# 2SiPM_4.net
KiCad netlist of a schematic drawn in Altium Designer
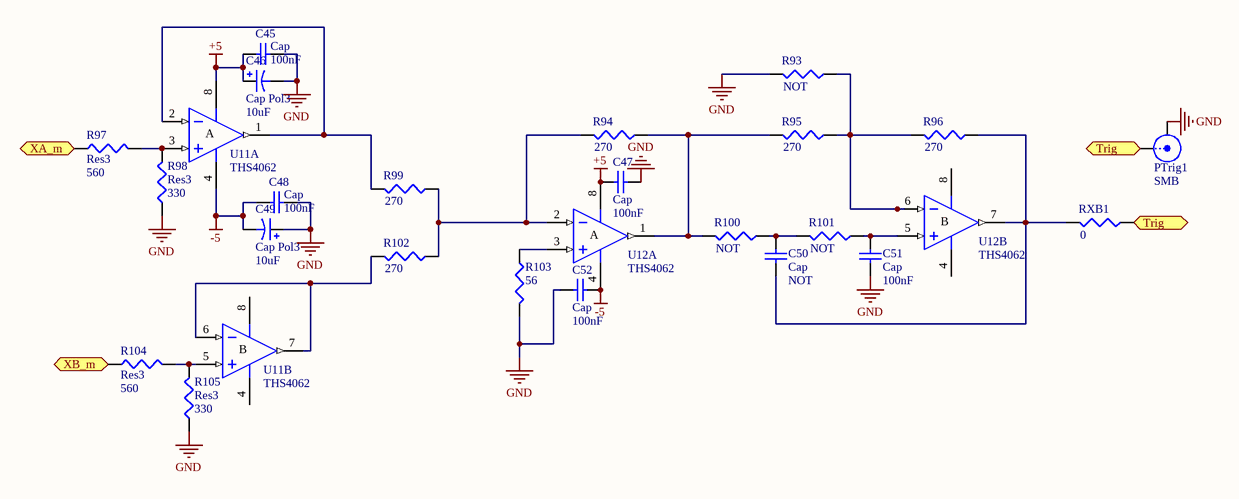
[diagram p0: 2SiPM_4.SchDoc]

(export (version "E")
  (design (tool "Eeschema 10.0.6"))
  (components
    (comp (ref "C45")
      (value "Cap")
      (footprint "6-0805_N")
      (description "Capacitor")
      (fields (field (name "ALTIUM_VALUE") "100nF") (field (name "PUBLISHER") "Altium Limited"))
      (libsource (lib "Miscellaneous Devices") (part "Cap"))
    )
    (comp (ref "C46")
      (value "Cap Pol3")
      (footprint "6-0805_N")
      (description "Polarized Capacitor (Surface Mount)")
      (fields (field (name "ALTIUM_VALUE") "10uF") (field (name "PUBLISHER") "Altium Limited"))
      (libsource (lib "Miscellaneous Devices") (part "Cap Pol3"))
    )
    (comp (ref "C47")
      (value "Cap")
      (footprint "1608[0603]")
      (description "Capacitor")
      (fields (field (name "ALTIUM_VALUE") "100nF") (field (name "PUBLISHER") "Altium Limited"))
      (libsource (lib "Miscellaneous Devices") (part "Cap"))
    )
    (comp (ref "C48")
      (value "Cap")
      (footprint "6-0805_N")
      (description "Capacitor")
      (fields (field (name "ALTIUM_VALUE") "100nF") (field (name "PUBLISHER") "Altium Limited"))
      (libsource (lib "Miscellaneous Devices") (part "Cap"))
    )
    (comp (ref "C49")
      (value "Cap Pol3")
      (footprint "6-0805_N")
      (description "Polarized Capacitor (Surface Mount)")
      (fields (field (name "ALTIUM_VALUE") "10uF") (field (name "PUBLISHER") "Altium Limited"))
      (libsource (lib "Miscellaneous Devices") (part "Cap Pol3"))
    )
    (comp (ref "C50")
      (value "Cap")
      (footprint "1608[0603]")
      (description "Capacitor")
      (fields (field (name "ALTIUM_VALUE") "NOT") (field (name "PUBLISHER") "Altium Limited"))
      (libsource (lib "Miscellaneous Devices") (part "Cap"))
    )
    (comp (ref "C51")
      (value "Cap")
      (footprint "1608[0603]")
      (description "Capacitor")
      (fields (field (name "ALTIUM_VALUE") "100nF") (field (name "PUBLISHER") "Altium Limited"))
      (libsource (lib "Miscellaneous Devices") (part "Cap"))
    )
    (comp (ref "C52")
      (value "Cap")
      (footprint "1608[0603]")
      (description "Capacitor")
      (fields (field (name "ALTIUM_VALUE") "100nF") (field (name "PUBLISHER") "Altium Limited"))
      (libsource (lib "Miscellaneous Devices") (part "Cap"))
    )
    (comp (ref "PTrig1")
      (value "SMB")
      (footprint "SMB_V-RJ45")
      (description "SMB Straight Connector")
      (fields (field (name "PUBLISHER") "Altium Limited"))
      (libsource (lib "Miscellaneous Connectors") (part "SMB"))
    )
    (comp (ref "R93")
      (value "NOT")
      (footprint "J1-0603")
      (description "Resistor")
      (fields (field (name "Comment") "Res3") (field (name "PUBLISHER") "Altium Limited"))
      (libsource (lib "Miscellaneous Devices") (part "Res3"))
    )
    (comp (ref "R94")
      (value "270")
      (footprint "J1-0603")
      (description "Resistor")
      (fields (field (name "Comment") "Res3") (field (name "PUBLISHER") "Altium Limited"))
      (libsource (lib "Miscellaneous Devices") (part "Res3"))
    )
    (comp (ref "R95")
      (value "270")
      (footprint "J1-0603")
      (description "Resistor")
      (fields (field (name "Comment") "Res3") (field (name "PUBLISHER") "Altium Limited"))
      (libsource (lib "Miscellaneous Devices") (part "Res3"))
    )
    (comp (ref "R96")
      (value "270")
      (footprint "J1-0603")
      (description "Resistor")
      (fields (field (name "Comment") "Res3") (field (name "PUBLISHER") "Altium Limited"))
      (libsource (lib "Miscellaneous Devices") (part "Res3"))
    )
    (comp (ref "R97")
      (value "Res3")
      (footprint "J1-0603")
      (description "Resistor")
      (fields (field (name "ALTIUM_VALUE") "560") (field (name "PUBLISHER") "Altium Limited"))
      (libsource (lib "Miscellaneous Devices") (part "Res3"))
    )
    (comp (ref "R98")
      (value "Res3")
      (footprint "J1-0603")
      (description "Resistor")
      (fields (field (name "ALTIUM_VALUE") "330") (field (name "PUBLISHER") "Altium Limited"))
      (libsource (lib "Miscellaneous Devices") (part "Res3"))
    )
    (comp (ref "R99")
      (value "270")
      (footprint "J1-0603")
      (description "Resistor")
      (fields (field (name "Comment") "Res3") (field (name "PUBLISHER") "Altium Limited"))
      (libsource (lib "Miscellaneous Devices") (part "Res3"))
    )
    (comp (ref "R100")
      (value "NOT")
      (footprint "J1-0603")
      (description "Resistor")
      (fields (field (name "Comment") "Res3") (field (name "PUBLISHER") "Altium Limited"))
      (libsource (lib "Miscellaneous Devices") (part "Res3"))
    )
    (comp (ref "R101")
      (value "NOT")
      (footprint "J1-0603")
      (description "Resistor")
      (fields (field (name "Comment") "Res3") (field (name "PUBLISHER") "Altium Limited"))
      (libsource (lib "Miscellaneous Devices") (part "Res3"))
    )
    (comp (ref "R102")
      (value "270")
      (footprint "J1-0603")
      (description "Resistor")
      (fields (field (name "Comment") "Res3") (field (name "PUBLISHER") "Altium Limited"))
      (libsource (lib "Miscellaneous Devices") (part "Res3"))
    )
    (comp (ref "R103")
      (value "56")
      (footprint "J1-0603")
      (description "Resistor")
      (fields (field (name "Comment") "Res3") (field (name "PUBLISHER") "Altium Limited"))
      (libsource (lib "Miscellaneous Devices") (part "Res3"))
    )
    (comp (ref "R104")
      (value "Res3")
      (footprint "J1-0603")
      (description "Resistor")
      (fields (field (name "ALTIUM_VALUE") "560") (field (name "PUBLISHER") "Altium Limited"))
      (libsource (lib "Miscellaneous Devices") (part "Res3"))
    )
    (comp (ref "R105")
      (value "Res3")
      (footprint "J1-0603")
      (description "Resistor")
      (fields (field (name "ALTIUM_VALUE") "330") (field (name "PUBLISHER") "Altium Limited"))
      (libsource (lib "Miscellaneous Devices") (part "Res3"))
    )
    (comp (ref "RXB1")
      (value "0")
      (footprint "J1-0603")
      (description "Resistor")
      (fields (field (name "Comment") "Res3") (field (name "PUBLISHER") "Altium Limited"))
      (libsource (lib "Miscellaneous Devices") (part "Res3"))
    )
    (comp (ref "U11")
      (value "THS4062")
      (footprint "SO-8_M")
      (description "Dual 600MHz, 50mW Current Feedback Amplifier")
      (fields (field (name "PUBLISHER") "Altium Limited"))
      (libsource (lib "AD Operational Amplifier") (part "AD8002AR"))
    )
    (comp (ref "U12")
      (value "THS4062")
      (footprint "SO8_M")
      (description "Low Cost, 300MHz Voltage Feedback Amplifier")
      (fields (field (name "PUBLISHER") "Altium Limited"))
      (libsource (lib "AD Operational Amplifier") (part "AD8056ARM"))
    )
  )
  (nets
    (net (code "1") (name "+5") (class "Default")
      (node (ref "C45") (pin "2") (pinfunction "2_2") (pintype "passive"))
      (node (ref "C46") (pin "1") (pinfunction "1_1") (pintype "passive"))
      (node (ref "C47") (pin "1") (pinfunction "1_1") (pintype "passive"))
      (node (ref "U11") (pin "8") (pinfunction "V+_8") (pintype "power_in"))
      (node (ref "U12") (pin "8") (pinfunction "V+_8") (pintype "power_in"))
    )
    (net (code "2") (name "-5") (class "Default")
      (node (ref "C48") (pin "2") (pinfunction "2_2") (pintype "passive"))
      (node (ref "C49") (pin "2") (pinfunction "2_2") (pintype "passive"))
      (node (ref "C52") (pin "2") (pinfunction "2_2") (pintype "passive"))
      (node (ref "U11") (pin "4") (pinfunction "V-_4") (pintype "power_in"))
      (node (ref "U12") (pin "4") (pinfunction "V-_4") (pintype "power_in"))
    )
    (net (code "3") (name "/Trig") (class "Default")
      (node (ref "PTrig1") (pin "1") (pinfunction "X_1") (pintype "passive"))
      (node (ref "RXB1") (pin "1") (pinfunction "1_1") (pintype "passive"))
    )
    (net (code "4") (name "/XA_m") (class "Default")
      (node (ref "R97") (pin "1") (pinfunction "1_1") (pintype "passive"))
    )
    (net (code "5") (name "/XB_m") (class "Default")
      (node (ref "R104") (pin "1") (pinfunction "1_1") (pintype "passive"))
    )
    (net (code "6") (name "GND") (class "Default")
      (node (ref "C45") (pin "1") (pinfunction "1_1") (pintype "passive"))
      (node (ref "C46") (pin "2") (pinfunction "2_2") (pintype "passive"))
      (node (ref "C47") (pin "2") (pinfunction "2_2") (pintype "passive"))
      (node (ref "C48") (pin "1") (pinfunction "1_1") (pintype "passive"))
      (node (ref "C49") (pin "1") (pinfunction "1_1") (pintype "passive"))
      (node (ref "C51") (pin "2") (pinfunction "2_2") (pintype "passive"))
      (node (ref "C52") (pin "1") (pinfunction "1_1") (pintype "passive"))
      (node (ref "PTrig1") (pin "2") (pinfunction "Y_2") (pintype "passive"))
      (node (ref "R103") (pin "2") (pinfunction "2_2") (pintype "passive"))
      (node (ref "R105") (pin "1") (pinfunction "1_1") (pintype "passive"))
      (node (ref "R93") (pin "2") (pinfunction "2_2") (pintype "passive"))
      (node (ref "R98") (pin "1") (pinfunction "1_1") (pintype "passive"))
    )
    (net (code "7") (name "Net-(C50-Pad1)") (class "Default")
      (node (ref "C50") (pin "1") (pinfunction "1_1") (pintype "passive"))
      (node (ref "R100") (pin "1") (pinfunction "1_1") (pintype "passive"))
      (node (ref "R101") (pin "2") (pinfunction "2_2") (pintype "passive"))
    )
    (net (code "8") (name "Net-(U11A-IN+)") (class "Default")
      (node (ref "R97") (pin "2") (pinfunction "2_2") (pintype "passive"))
      (node (ref "R98") (pin "2") (pinfunction "2_2") (pintype "passive"))
      (node (ref "U11") (pin "3") (pinfunction "IN+_3") (pintype "input"))
    )
    (net (code "9") (name "Net-(U11A-IN-)") (class "Default")
      (node (ref "R99") (pin "2") (pinfunction "2_2") (pintype "passive"))
      (node (ref "U11") (pin "1") (pinfunction "OUT_1") (pintype "output"))
      (node (ref "U11") (pin "2") (pinfunction "IN-_2") (pintype "input"))
    )
    (net (code "10") (name "Net-(U11B-IN+)") (class "Default")
      (node (ref "R104") (pin "2") (pinfunction "2_2") (pintype "passive"))
      (node (ref "R105") (pin "2") (pinfunction "2_2") (pintype "passive"))
      (node (ref "U11") (pin "5") (pinfunction "IN+_5") (pintype "input"))
    )
    (net (code "11") (name "Net-(U11B-IN-)") (class "Default")
      (node (ref "R102") (pin "2") (pinfunction "2_2") (pintype "passive"))
      (node (ref "U11") (pin "6") (pinfunction "IN-_6") (pintype "input"))
      (node (ref "U11") (pin "7") (pinfunction "OUT_7") (pintype "output"))
    )
    (net (code "12") (name "Net-(U12A-IN+)") (class "Default")
      (node (ref "R103") (pin "1") (pinfunction "1_1") (pintype "passive"))
      (node (ref "U12") (pin "3") (pinfunction "IN+_3") (pintype "input"))
    )
    (net (code "13") (name "Net-(U12A-IN-)") (class "Default")
      (node (ref "R102") (pin "1") (pinfunction "1_1") (pintype "passive"))
      (node (ref "R94") (pin "2") (pinfunction "2_2") (pintype "passive"))
      (node (ref "R99") (pin "1") (pinfunction "1_1") (pintype "passive"))
      (node (ref "U12") (pin "2") (pinfunction "IN-_2") (pintype "input"))
    )
    (net (code "14") (name "Net-(U12A-OUT)") (class "Default")
      (node (ref "R100") (pin "2") (pinfunction "2_2") (pintype "passive"))
      (node (ref "R94") (pin "1") (pinfunction "1_1") (pintype "passive"))
      (node (ref "R95") (pin "2") (pinfunction "2_2") (pintype "passive"))
      (node (ref "U12") (pin "1") (pinfunction "OUT_1") (pintype "output"))
    )
    (net (code "15") (name "Net-(U12B-IN+)") (class "Default")
      (node (ref "C51") (pin "1") (pinfunction "1_1") (pintype "passive"))
      (node (ref "R101") (pin "1") (pinfunction "1_1") (pintype "passive"))
      (node (ref "U12") (pin "5") (pinfunction "IN+_5") (pintype "input"))
    )
    (net (code "16") (name "Net-(U12B-IN-)") (class "Default")
      (node (ref "R93") (pin "1") (pinfunction "1_1") (pintype "passive"))
      (node (ref "R95") (pin "1") (pinfunction "1_1") (pintype "passive"))
      (node (ref "R96") (pin "2") (pinfunction "2_2") (pintype "passive"))
      (node (ref "U12") (pin "6") (pinfunction "IN-_6") (pintype "input"))
    )
    (net (code "17") (name "Net-(U12B-OUT)") (class "Default")
      (node (ref "C50") (pin "2") (pinfunction "2_2") (pintype "passive"))
      (node (ref "R96") (pin "1") (pinfunction "1_1") (pintype "passive"))
      (node (ref "RXB1") (pin "2") (pinfunction "2_2") (pintype "passive"))
      (node (ref "U12") (pin "7") (pinfunction "OUT_7") (pintype "output"))
    )
    (net (code "18") (name "unconnected-(U11B-V+-Pad8)") (class "Default")
      (node (ref "U11") (pin "8") (pinfunction "V+_8") (pintype "power_in"))
    )
    (net (code "19") (name "unconnected-(U11B-V--Pad4)") (class "Default")
      (node (ref "U11") (pin "4") (pinfunction "V-_4") (pintype "power_in"))
    )
    (net (code "20") (name "unconnected-(U12B-V+-Pad8)") (class "Default")
      (node (ref "U12") (pin "8") (pinfunction "V+_8") (pintype "power_in"))
    )
    (net (code "21") (name "unconnected-(U12B-V--Pad4)") (class "Default")
      (node (ref "U12") (pin "4") (pinfunction "V-_4") (pintype "power_in"))
    )
  )
)
